# Motor_control_logic.net
KiCad netlist of a schematic drawn in Altium Designer
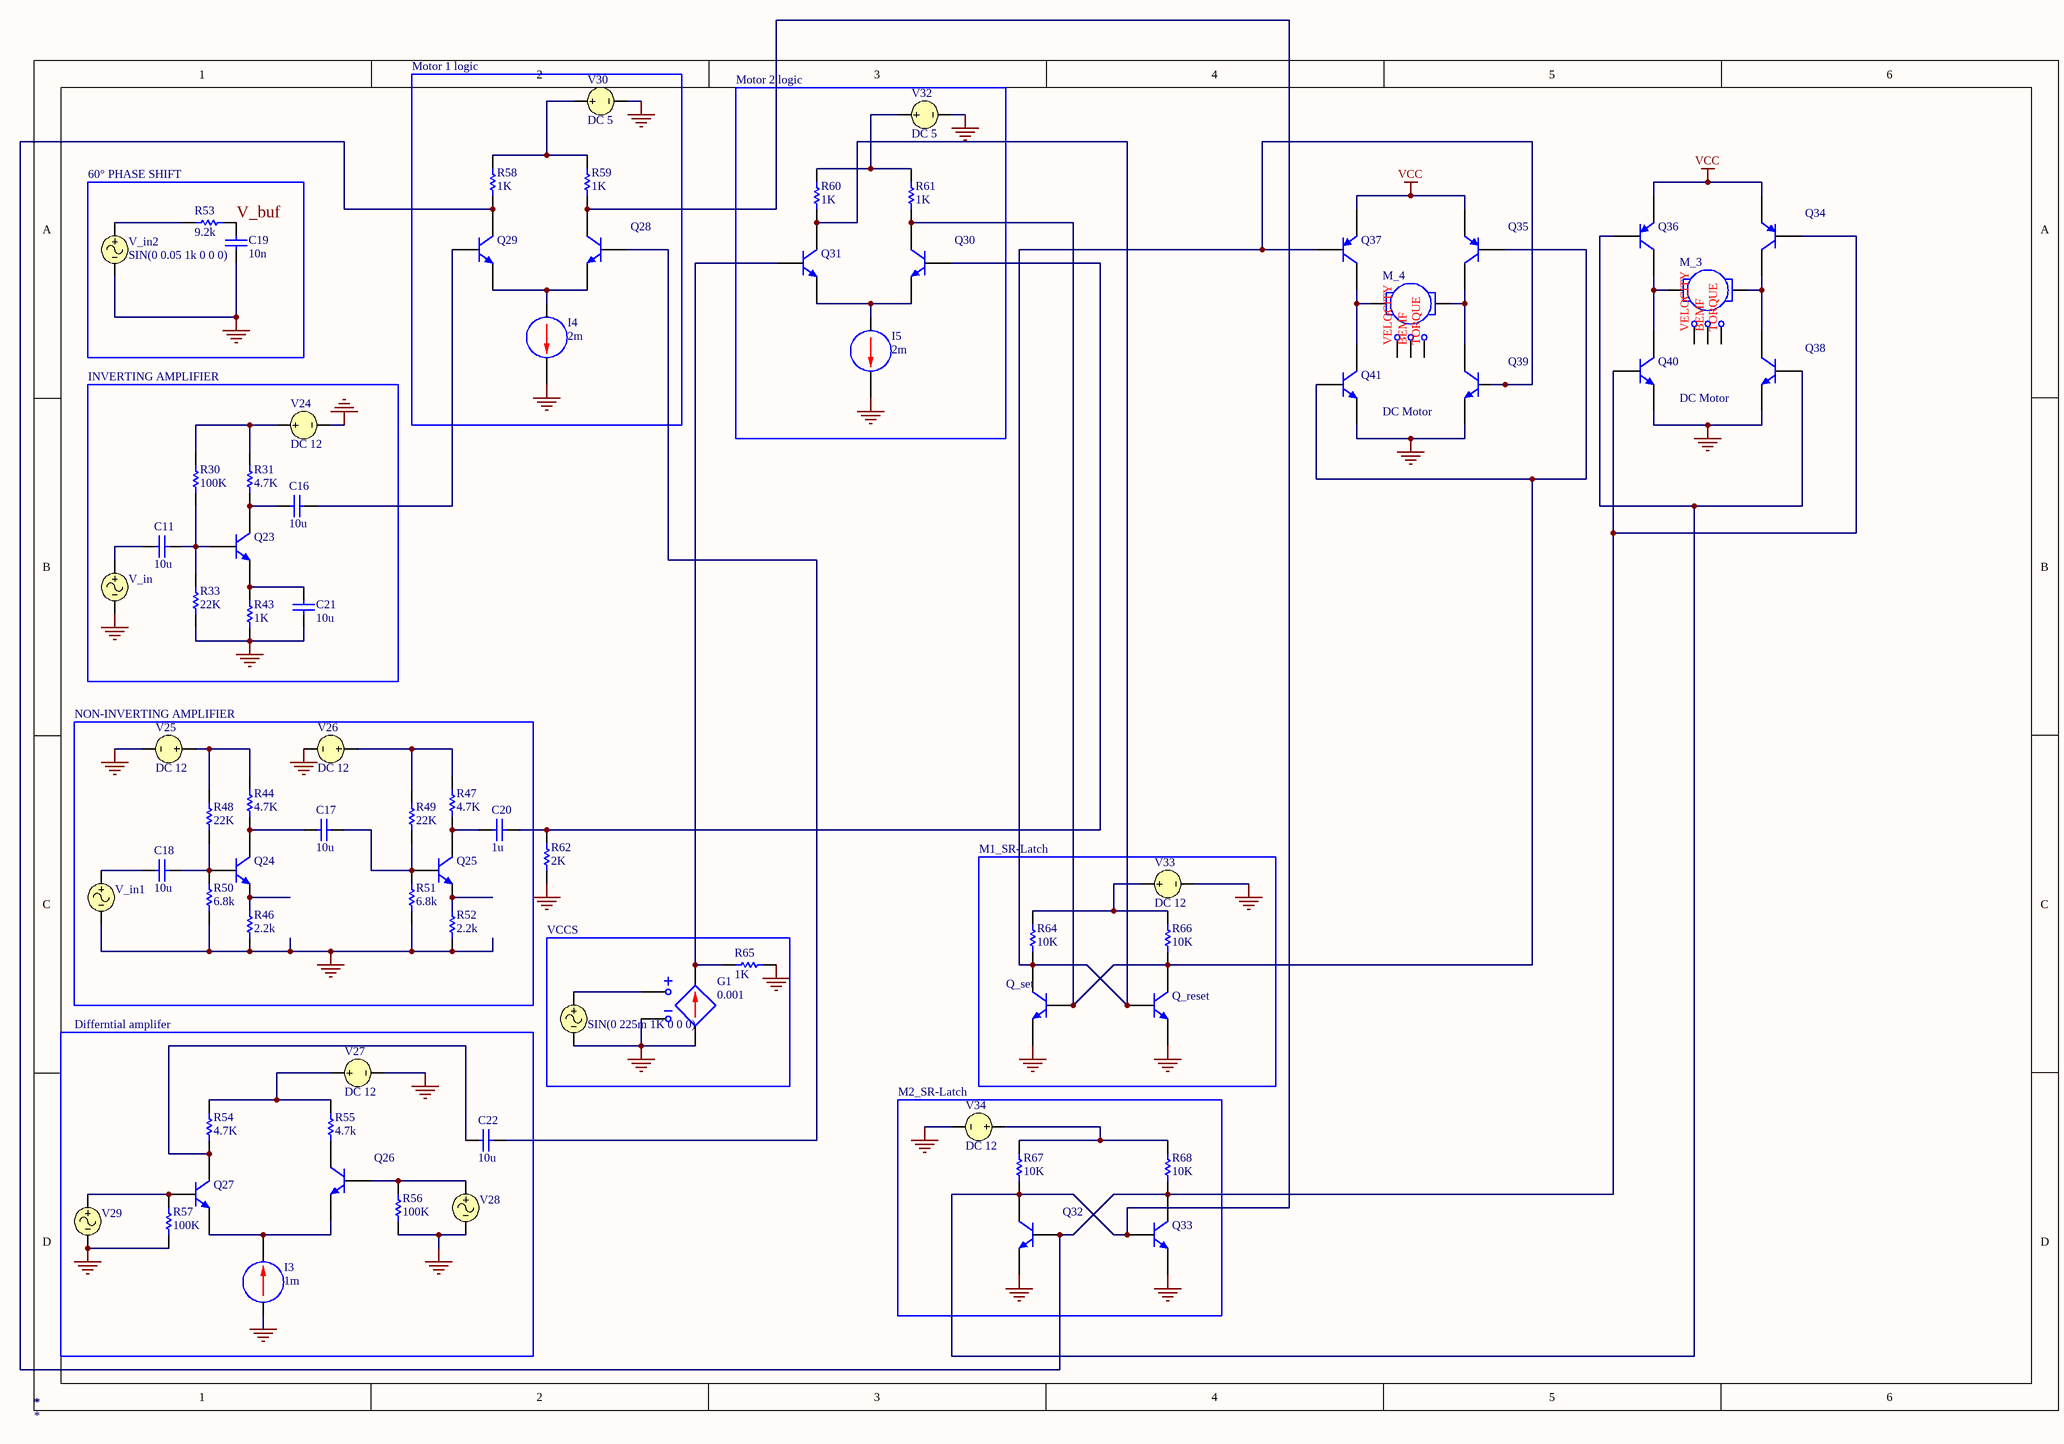
[diagram p0: Motor control logic.SchDoc]

(export (version "E")
  (design (tool "Eeschema 10.0.6"))
  (components
    (comp (ref "C11")
      (value "10u")
      (description "Capacitor")
      (libsource (lib "Simulation Generic Components") (part "Capacitor"))
    )
    (comp (ref "C16")
      (value "10u")
      (description "Capacitor")
      (libsource (lib "Simulation Generic Components") (part "Capacitor"))
    )
    (comp (ref "C17")
      (value "10u")
      (description "Capacitor")
      (libsource (lib "Simulation Generic Components") (part "Capacitor"))
    )
    (comp (ref "C18")
      (value "10u")
      (description "Capacitor")
      (libsource (lib "Simulation Generic Components") (part "Capacitor"))
    )
    (comp (ref "C19")
      (value "10n")
      (description "Capacitor")
      (libsource (lib "Simulation Generic Components") (part "Capacitor"))
    )
    (comp (ref "C20")
      (value "1u")
      (description "Capacitor")
      (libsource (lib "Simulation Generic Components") (part "Capacitor"))
    )
    (comp (ref "C21")
      (value "10u")
      (description "Capacitor")
      (libsource (lib "Simulation Generic Components") (part "Capacitor"))
    )
    (comp (ref "C22")
      (value "10u")
      (description "Capacitor")
      (libsource (lib "Simulation Generic Components") (part "Capacitor"))
    )
    (comp (ref "G1")
      (value "Voltage Controlled Current Source")
      (fields (field (name "GAIN") "0.001"))
      (libsource (lib "Simulation Generic Components") (part "VCCS"))
    )
    (comp (ref "I3")
      (value "DC Current Source")
      (fields (field (name "DC") "1m"))
      (libsource (lib "Simulation Generic Components") (part "DC Current Source"))
    )
    (comp (ref "I4")
      (value "DC Current Source")
      (fields (field (name "DC") "2m"))
      (libsource (lib "Simulation Generic Components") (part "DC Current Source"))
    )
    (comp (ref "I5")
      (value "DC Current Source")
      (fields (field (name "DC") "2m"))
      (libsource (lib "Simulation Generic Components") (part "DC Current Source"))
    )
    (comp (ref "M_3") (value "DC Motor") (libsource (lib "Simulation Generic Components") (part "DC Motor")))
    (comp (ref "M_4") (value "DC Motor") (libsource (lib "Simulation Generic Components") (part "DC Motor")))
    (comp (ref "Q23")
      (value "Bipolar NPN 3 Pins Transistor VBIC Model")
      (libsource (lib "Simulation Generic Components") (part "BJT NPN VBIC"))
    )
    (comp (ref "Q24")
      (value "Bipolar NPN 3 Pins Transistor Modified Version of the Gummel-Poon Model")
      (libsource (lib "Simulation Generic Components") (part "BJT NPN_MGP"))
    )
    (comp (ref "Q25")
      (value "Bipolar NPN 3 Pins Transistor Modified Version of the Gummel-Poon Model")
      (libsource (lib "Simulation Generic Components") (part "BJT NPN_MGP"))
    )
    (comp (ref "Q26")
      (value "Bipolar NPN 3 Pins Transistor VBIC Model")
      (libsource (lib "Simulation Generic Components") (part "BJT NPN VBIC"))
    )
    (comp (ref "Q27")
      (value "Bipolar NPN 3 Pins Transistor VBIC Model")
      (libsource (lib "Simulation Generic Components") (part "BJT NPN VBIC"))
    )
    (comp (ref "Q28")
      (value "Bipolar NPN 3 Pins Transistor Modified Version of the Gummel-Poon Model")
      (libsource (lib "Simulation Generic Components") (part "BJT NPN_MGP"))
    )
    (comp (ref "Q29")
      (value "Bipolar NPN 3 Pins Transistor Modified Version of the Gummel-Poon Model")
      (libsource (lib "Simulation Generic Components") (part "BJT NPN_MGP"))
    )
    (comp (ref "Q30")
      (value "Bipolar NPN 3 Pins Transistor Modified Version of the Gummel-Poon Model")
      (libsource (lib "Simulation Generic Components") (part "BJT NPN_MGP"))
    )
    (comp (ref "Q31")
      (value "Bipolar NPN 3 Pins Transistor Modified Version of the Gummel-Poon Model")
      (libsource (lib "Simulation Generic Components") (part "BJT NPN_MGP"))
    )
    (comp (ref "Q32")
      (value "Bipolar NPN 3 Pins Transistor VBIC Model")
      (libsource (lib "Simulation Generic Components") (part "BJT NPN VBIC"))
    )
    (comp (ref "Q33")
      (value "Bipolar NPN 3 Pins Transistor VBIC Model")
      (libsource (lib "Simulation Generic Components") (part "BJT NPN VBIC"))
    )
    (comp (ref "Q34")
      (value "Bipolar PNP 3 Pins Transistor Gummel-Poon Model")
      (libsource (lib "Simulation Generic Components") (part "BJT PNP GP"))
    )
    (comp (ref "Q35")
      (value "Bipolar PNP 3 Pins Transistor Gummel-Poon Model")
      (libsource (lib "Simulation Generic Components") (part "BJT PNP GP"))
    )
    (comp (ref "Q36")
      (value "Bipolar PNP 3 Pins Transistor Gummel-Poon Model")
      (libsource (lib "Simulation Generic Components") (part "BJT PNP GP"))
    )
    (comp (ref "Q37")
      (value "Bipolar PNP 3 Pins Transistor Gummel-Poon Model")
      (libsource (lib "Simulation Generic Components") (part "BJT PNP GP"))
    )
    (comp (ref "Q38")
      (value "Bipolar NPN 3 Pins Transistor VBIC Model")
      (libsource (lib "Simulation Generic Components") (part "BJT NPN VBIC"))
    )
    (comp (ref "Q39")
      (value "Bipolar NPN 3 Pins Transistor VBIC Model")
      (libsource (lib "Simulation Generic Components") (part "BJT NPN VBIC"))
    )
    (comp (ref "Q40")
      (value "Bipolar NPN 3 Pins Transistor VBIC Model")
      (libsource (lib "Simulation Generic Components") (part "BJT NPN VBIC"))
    )
    (comp (ref "Q41")
      (value "Bipolar NPN 3 Pins Transistor VBIC Model")
      (libsource (lib "Simulation Generic Components") (part "BJT NPN VBIC"))
    )
    (comp (ref "Q_reset")
      (value "Bipolar NPN 3 Pins Transistor VBIC Model")
      (libsource (lib "Simulation Generic Components") (part "BJT NPN VBIC"))
    )
    (comp (ref "Q_set")
      (value "Bipolar NPN 3 Pins Transistor VBIC Model")
      (libsource (lib "Simulation Generic Components") (part "BJT NPN VBIC"))
    )
    (comp (ref "R30")
      (value "100K")
      (description "Resistor")
      (libsource (lib "Simulation Generic Components") (part "Resistor"))
    )
    (comp (ref "R31")
      (value "4.7K")
      (description "Resistor")
      (libsource (lib "Simulation Generic Components") (part "Resistor"))
    )
    (comp (ref "R33")
      (value "22K")
      (description "Resistor")
      (libsource (lib "Simulation Generic Components") (part "Resistor"))
    )
    (comp (ref "R43")
      (value "1K")
      (description "Resistor")
      (libsource (lib "Simulation Generic Components") (part "Resistor"))
    )
    (comp (ref "R44")
      (value "4.7K")
      (description "Resistor")
      (libsource (lib "Simulation Generic Components") (part "Resistor"))
    )
    (comp (ref "R46")
      (value "2.2k")
      (description "Resistor")
      (libsource (lib "Simulation Generic Components") (part "Resistor"))
    )
    (comp (ref "R47")
      (value "4.7K")
      (description "Resistor")
      (libsource (lib "Simulation Generic Components") (part "Resistor"))
    )
    (comp (ref "R48")
      (value "22K")
      (description "Resistor")
      (libsource (lib "Simulation Generic Components") (part "Resistor"))
    )
    (comp (ref "R49")
      (value "22K")
      (description "Resistor")
      (libsource (lib "Simulation Generic Components") (part "Resistor"))
    )
    (comp (ref "R50")
      (value "6.8k")
      (description "Resistor")
      (libsource (lib "Simulation Generic Components") (part "Resistor"))
    )
    (comp (ref "R51")
      (value "6.8k")
      (description "Resistor")
      (libsource (lib "Simulation Generic Components") (part "Resistor"))
    )
    (comp (ref "R52")
      (value "2.2k")
      (description "Resistor")
      (libsource (lib "Simulation Generic Components") (part "Resistor"))
    )
    (comp (ref "R53")
      (value "9.2k")
      (description "Resistor")
      (libsource (lib "Simulation Generic Components") (part "Resistor"))
    )
    (comp (ref "R54")
      (value "4.7K")
      (description "Resistor")
      (libsource (lib "Simulation Generic Components") (part "Resistor"))
    )
    (comp (ref "R55")
      (value "4.7k")
      (description "Resistor")
      (libsource (lib "Simulation Generic Components") (part "Resistor"))
    )
    (comp (ref "R56")
      (value "100K")
      (description "Resistor")
      (libsource (lib "Simulation Generic Components") (part "Resistor"))
    )
    (comp (ref "R57")
      (value "100K")
      (description "Resistor")
      (libsource (lib "Simulation Generic Components") (part "Resistor"))
    )
    (comp (ref "R58")
      (value "1K")
      (description "Resistor")
      (libsource (lib "Simulation Generic Components") (part "Resistor"))
    )
    (comp (ref "R59")
      (value "1K")
      (description "Resistor")
      (libsource (lib "Simulation Generic Components") (part "Resistor"))
    )
    (comp (ref "R60")
      (value "1K")
      (description "Resistor")
      (libsource (lib "Simulation Generic Components") (part "Resistor"))
    )
    (comp (ref "R61")
      (value "1K")
      (description "Resistor")
      (libsource (lib "Simulation Generic Components") (part "Resistor"))
    )
    (comp (ref "R62")
      (value "2K")
      (description "Resistor")
      (libsource (lib "Simulation Generic Components") (part "Resistor"))
    )
    (comp (ref "R64")
      (value "10K")
      (description "Resistor")
      (libsource (lib "Simulation Generic Components") (part "Resistor"))
    )
    (comp (ref "R65")
      (value "1K")
      (description "Resistor")
      (libsource (lib "Simulation Generic Components") (part "Resistor"))
    )
    (comp (ref "R66")
      (value "10K")
      (description "Resistor")
      (libsource (lib "Simulation Generic Components") (part "Resistor"))
    )
    (comp (ref "R67")
      (value "10K")
      (description "Resistor")
      (libsource (lib "Simulation Generic Components") (part "Resistor"))
    )
    (comp (ref "R68")
      (value "10K")
      (description "Resistor")
      (libsource (lib "Simulation Generic Components") (part "Resistor"))
    )
    (comp (ref "V24")
      (value "DC 12")
      (description "Voltage Source")
      (fields (field (name "PUBLISHER") "Altium Limited"))
      (libsource (lib "Simulation Generic Components") (part "VSRC"))
    )
    (comp (ref "V25")
      (value "DC 12")
      (description "Voltage Source")
      (fields (field (name "PUBLISHER") "Altium Limited"))
      (libsource (lib "Simulation Generic Components") (part "VSRC"))
    )
    (comp (ref "V26")
      (value "DC 12")
      (description "Voltage Source")
      (fields (field (name "PUBLISHER") "Altium Limited"))
      (libsource (lib "Simulation Generic Components") (part "VSRC"))
    )
    (comp (ref "V27")
      (value "DC 12")
      (description "Voltage Source")
      (fields (field (name "PUBLISHER") "Altium Limited"))
      (libsource (lib "Simulation Generic Components") (part "VSRC"))
    )
    (comp (ref "V28")
      (value "SIN(0 50m 1K 0 0 60)")
      (description "Sinusoidal Voltage Source")
      (fields (field (name "PUBLISHER") "Altium Limited"))
      (libsource (lib "Simulation Generic Components") (part "VSIN"))
    )
    (comp (ref "V29")
      (value "SIN(0 50m 1K 0 0 0)")
      (description "Sinusoidal Voltage Source")
      (fields (field (name "PUBLISHER") "Altium Limited"))
      (libsource (lib "Simulation Generic Components") (part "VSIN"))
    )
    (comp (ref "V30")
      (value "DC 5")
      (description "Voltage Source")
      (fields (field (name "PUBLISHER") "Altium Limited"))
      (libsource (lib "Simulation Generic Components") (part "VSRC"))
    )
    (comp (ref "V31")
      (value "SIN(0 225m 1K 0 0 0)")
      (description "Sinusoidal Voltage Source")
      (fields (field (name "PUBLISHER") "Altium Limited"))
      (libsource (lib "Simulation Generic Components") (part "VSIN"))
    )
    (comp (ref "V32")
      (value "DC 5")
      (description "Voltage Source")
      (fields (field (name "PUBLISHER") "Altium Limited"))
      (libsource (lib "Simulation Generic Components") (part "VSRC"))
    )
    (comp (ref "V33")
      (value "DC 12")
      (description "Voltage Source")
      (fields (field (name "PUBLISHER") "Altium Limited"))
      (libsource (lib "Simulation Generic Components") (part "VSRC"))
    )
    (comp (ref "V34")
      (value "DC 12")
      (description "Voltage Source")
      (fields (field (name "PUBLISHER") "Altium Limited"))
      (libsource (lib "Simulation Generic Components") (part "VSRC"))
    )
    (comp (ref "V_in")
      (value "SIN(0 0.1 1K 0 0 0)")
      (description "Sinusoidal Voltage Source")
      (fields (field (name "PUBLISHER") "Altium Limited"))
      (libsource (lib "Simulation Generic Components") (part "VSIN"))
    )
    (comp (ref "V_in1")
      (value "SIN(0 0.1 1K 0 0 0)")
      (description "Sinusoidal Voltage Source")
      (fields (field (name "PUBLISHER") "Altium Limited"))
      (libsource (lib "Simulation Generic Components") (part "VSIN"))
    )
    (comp (ref "V_in2")
      (value "SIN(0 0.05 1k 0 0 0)")
      (description "Sinusoidal Voltage Source")
      (fields (field (name "PUBLISHER") "Altium Limited"))
      (libsource (lib "Simulation Generic Components") (part "VSIN"))
    )
  )
  (nets
    (net (code "1") (name "/V_buf") (class "Default")
      (node (ref "C19") (pin "2") (pinfunction "2_2") (pintype "passive"))
      (node (ref "R53") (pin "2") (pinfunction "2_2") (pintype "passive"))
    )
    (net (code "2") (name "GND") (class "Default")
      (node (ref "C19") (pin "1") (pinfunction "1_1") (pintype "passive"))
      (node (ref "C21") (pin "1") (pinfunction "1_1") (pintype "passive"))
      (node (ref "G1") (pin "2") (pinfunction "2_2") (pintype "passive"))
      (node (ref "G1") (pin "4") (pinfunction "4_4") (pintype "passive"))
      (node (ref "I3") (pin "2") (pinfunction "-_2") (pintype "passive"))
      (node (ref "I4") (pin "1") (pinfunction "+_1") (pintype "passive"))
      (node (ref "I5") (pin "1") (pinfunction "+_1") (pintype "passive"))
      (node (ref "Q32") (pin "3") (pinfunction "E_3") (pintype "passive"))
      (node (ref "Q33") (pin "3") (pinfunction "E_3") (pintype "passive"))
      (node (ref "Q38") (pin "3") (pinfunction "E_3") (pintype "passive"))
      (node (ref "Q39") (pin "3") (pinfunction "E_3") (pintype "passive"))
      (node (ref "Q40") (pin "3") (pinfunction "E_3") (pintype "passive"))
      (node (ref "Q41") (pin "3") (pinfunction "E_3") (pintype "passive"))
      (node (ref "Q_reset") (pin "3") (pinfunction "E_3") (pintype "passive"))
      (node (ref "Q_set") (pin "3") (pinfunction "E_3") (pintype "passive"))
      (node (ref "R33") (pin "1") (pinfunction "1_1") (pintype "passive"))
      (node (ref "R43") (pin "1") (pinfunction "1_1") (pintype "passive"))
      (node (ref "R46") (pin "1") (pinfunction "1_1") (pintype "passive"))
      (node (ref "R50") (pin "1") (pinfunction "1_1") (pintype "passive"))
      (node (ref "R51") (pin "1") (pinfunction "1_1") (pintype "passive"))
      (node (ref "R52") (pin "1") (pinfunction "1_1") (pintype "passive"))
      (node (ref "R56") (pin "1") (pinfunction "1_1") (pintype "passive"))
      (node (ref "R57") (pin "1") (pinfunction "1_1") (pintype "passive"))
      (node (ref "R62") (pin "1") (pinfunction "1_1") (pintype "passive"))
      (node (ref "R65") (pin "2") (pinfunction "2_2") (pintype "passive"))
      (node (ref "V24") (pin "2") (pinfunction "2_2") (pintype "passive"))
      (node (ref "V25") (pin "2") (pinfunction "2_2") (pintype "passive"))
      (node (ref "V26") (pin "2") (pinfunction "2_2") (pintype "passive"))
      (node (ref "V27") (pin "2") (pinfunction "2_2") (pintype "passive"))
      (node (ref "V28") (pin "2") (pinfunction "2_2") (pintype "passive"))
      (node (ref "V29") (pin "2") (pinfunction "2_2") (pintype "passive"))
      (node (ref "V30") (pin "2") (pinfunction "2_2") (pintype "passive"))
      (node (ref "V31") (pin "2") (pinfunction "2_2") (pintype "passive"))
      (node (ref "V32") (pin "2") (pinfunction "2_2") (pintype "passive"))
      (node (ref "V33") (pin "2") (pinfunction "2_2") (pintype "passive"))
      (node (ref "V34") (pin "2") (pinfunction "2_2") (pintype "passive"))
      (node (ref "V_in") (pin "2") (pinfunction "2_2") (pintype "passive"))
      (node (ref "V_in1") (pin "2") (pinfunction "2_2") (pintype "passive"))
      (node (ref "V_in2") (pin "2") (pinfunction "2_2") (pintype "passive"))
    )
    (net (code "3") (name "Net-(C11-Pad1)") (class "Default")
      (node (ref "C11") (pin "1") (pinfunction "1_1") (pintype "passive"))
      (node (ref "V_in") (pin "1") (pinfunction "1_1") (pintype "passive"))
    )
    (net (code "4") (name "Net-(C18-Pad1)") (class "Default")
      (node (ref "C18") (pin "1") (pinfunction "1_1") (pintype "passive"))
      (node (ref "V_in1") (pin "1") (pinfunction "1_1") (pintype "passive"))
    )
    (net (code "5") (name "Net-(G1-Pad3)") (class "Default")
      (node (ref "G1") (pin "3") (pinfunction "3_3") (pintype "passive"))
      (node (ref "V31") (pin "1") (pinfunction "1_1") (pintype "passive"))
    )
    (net (code "6") (name "Net-(I3-+)") (class "Default")
      (node (ref "I3") (pin "1") (pinfunction "+_1") (pintype "passive"))
      (node (ref "Q26") (pin "3") (pinfunction "E_3") (pintype "passive"))
      (node (ref "Q27") (pin "3") (pinfunction "E_3") (pintype "passive"))
    )
    (net (code "7") (name "Net-(I4--)") (class "Default")
      (node (ref "I4") (pin "2") (pinfunction "-_2") (pintype "passive"))
      (node (ref "Q28") (pin "3") (pinfunction "E_3") (pintype "passive"))
      (node (ref "Q29") (pin "3") (pinfunction "E_3") (pintype "passive"))
    )
    (net (code "8") (name "Net-(I5--)") (class "Default")
      (node (ref "I5") (pin "2") (pinfunction "-_2") (pintype "passive"))
      (node (ref "Q30") (pin "3") (pinfunction "E_3") (pintype "passive"))
      (node (ref "Q31") (pin "3") (pinfunction "E_3") (pintype "passive"))
    )
    (net (code "9") (name "Net-(Q23-B)") (class "Default")
      (node (ref "C11") (pin "2") (pinfunction "2_2") (pintype "passive"))
      (node (ref "Q23") (pin "2") (pinfunction "B_2") (pintype "passive"))
      (node (ref "R30") (pin "1") (pinfunction "1_1") (pintype "passive"))
      (node (ref "R33") (pin "2") (pinfunction "2_2") (pintype "passive"))
    )
    (net (code "10") (name "Net-(Q23-C)") (class "Default")
      (node (ref "C16") (pin "1") (pinfunction "1_1") (pintype "passive"))
      (node (ref "Q23") (pin "1") (pinfunction "C_1") (pintype "passive"))
      (node (ref "R31") (pin "1") (pinfunction "1_1") (pintype "passive"))
    )
    (net (code "11") (name "Net-(Q23-E)") (class "Default")
      (node (ref "C21") (pin "2") (pinfunction "2_2") (pintype "passive"))
      (node (ref "Q23") (pin "3") (pinfunction "E_3") (pintype "passive"))
      (node (ref "R43") (pin "2") (pinfunction "2_2") (pintype "passive"))
    )
    (net (code "12") (name "Net-(Q24-B)") (class "Default")
      (node (ref "C18") (pin "2") (pinfunction "2_2") (pintype "passive"))
      (node (ref "Q24") (pin "2") (pinfunction "B_2") (pintype "passive"))
      (node (ref "R48") (pin "1") (pinfunction "1_1") (pintype "passive"))
      (node (ref "R50") (pin "2") (pinfunction "2_2") (pintype "passive"))
    )
    (net (code "13") (name "Net-(Q24-C)") (class "Default")
      (node (ref "C17") (pin "1") (pinfunction "1_1") (pintype "passive"))
      (node (ref "Q24") (pin "1") (pinfunction "C_1") (pintype "passive"))
      (node (ref "R44") (pin "1") (pinfunction "1_1") (pintype "passive"))
    )
    (net (code "14") (name "Net-(Q24-E)") (class "Default")
      (node (ref "Q24") (pin "3") (pinfunction "E_3") (pintype "passive"))
      (node (ref "R46") (pin "2") (pinfunction "2_2") (pintype "passive"))
    )
    (net (code "15") (name "Net-(Q25-B)") (class "Default")
      (node (ref "C17") (pin "2") (pinfunction "2_2") (pintype "passive"))
      (node (ref "Q25") (pin "2") (pinfunction "B_2") (pintype "passive"))
      (node (ref "R49") (pin "1") (pinfunction "1_1") (pintype "passive"))
      (node (ref "R51") (pin "2") (pinfunction "2_2") (pintype "passive"))
    )
    (net (code "16") (name "Net-(Q25-C)") (class "Default")
      (node (ref "C20") (pin "1") (pinfunction "1_1") (pintype "passive"))
      (node (ref "Q25") (pin "1") (pinfunction "C_1") (pintype "passive"))
      (node (ref "R47") (pin "1") (pinfunction "1_1") (pintype "passive"))
    )
    (net (code "17") (name "Net-(Q25-E)") (class "Default")
      (node (ref "Q25") (pin "3") (pinfunction "E_3") (pintype "passive"))
      (node (ref "R52") (pin "2") (pinfunction "2_2") (pintype "passive"))
    )
    (net (code "18") (name "Net-(Q26-B)") (class "Default")
      (node (ref "Q26") (pin "2") (pinfunction "B_2") (pintype "passive"))
      (node (ref "R56") (pin "2") (pinfunction "2_2") (pintype "passive"))
      (node (ref "V28") (pin "1") (pinfunction "1_1") (pintype "passive"))
    )
    (net (code "19") (name "Net-(Q27-B)") (class "Default")
      (node (ref "Q27") (pin "2") (pinfunction "B_2") (pintype "passive"))
      (node (ref "R57") (pin "2") (pinfunction "2_2") (pintype "passive"))
      (node (ref "V29") (pin "1") (pinfunction "1_1") (pintype "passive"))
    )
    (net (code "20") (name "Net-(Q27-C)") (class "Default")
      (node (ref "C22") (pin "1") (pinfunction "1_1") (pintype "passive"))
      (node (ref "Q27") (pin "1") (pinfunction "C_1") (pintype "passive"))
      (node (ref "R54") (pin "1") (pinfunction "1_1") (pintype "passive"))
    )
    (net (code "21") (name "Net-(Q28-B)") (class "Default")
      (node (ref "C22") (pin "2") (pinfunction "2_2") (pintype "passive"))
      (node (ref "Q28") (pin "2") (pinfunction "B_2") (pintype "passive"))
    )
    (net (code "22") (name "Net-(Q28-C)") (class "Default")
      (node (ref "Q28") (pin "1") (pinfunction "C_1") (pintype "passive"))
      (node (ref "Q32") (pin "1") (pinfunction "C_1") (pintype "passive"))
      (node (ref "Q33") (pin "2") (pinfunction "B_2") (pintype "passive"))
      (node (ref "Q36") (pin "2") (pinfunction "B_2") (pintype "passive"))
      (node (ref "Q38") (pin "2") (pinfunction "B_2") (pintype "passive"))
      (node (ref "R59") (pin "1") (pinfunction "1_1") (pintype "passive"))
      (node (ref "R67") (pin "1") (pinfunction "1_1") (pintype "passive"))
    )
    (net (code "23") (name "Net-(Q29-B)") (class "Default")
      (node (ref "C16") (pin "2") (pinfunction "2_2") (pintype "passive"))
      (node (ref "Q29") (pin "2") (pinfunction "B_2") (pintype "passive"))
    )
    (net (code "24") (name "Net-(Q29-C)") (class "Default")
      (node (ref "Q29") (pin "1") (pinfunction "C_1") (pintype "passive"))
      (node (ref "Q32") (pin "2") (pinfunction "B_2") (pintype "passive"))
      (node (ref "Q33") (pin "1") (pinfunction "C_1") (pintype "passive"))
      (node (ref "Q34") (pin "2") (pinfunction "B_2") (pintype "passive"))
      (node (ref "Q40") (pin "2") (pinfunction "B_2") (pintype "passive"))
      (node (ref "R58") (pin "1") (pinfunction "1_1") (pintype "passive"))
      (node (ref "R68") (pin "1") (pinfunction "1_1") (pintype "passive"))
    )
    (net (code "25") (name "Net-(Q30-B)") (class "Default")
      (node (ref "C20") (pin "2") (pinfunction "2_2") (pintype "passive"))
      (node (ref "Q30") (pin "2") (pinfunction "B_2") (pintype "passive"))
      (node (ref "R62") (pin "2") (pinfunction "2_2") (pintype "passive"))
    )
    (net (code "26") (name "Net-(Q30-C)") (class "Default")
      (node (ref "Q30") (pin "1") (pinfunction "C_1") (pintype "passive"))
      (node (ref "Q35") (pin "2") (pinfunction "B_2") (pintype "passive"))
      (node (ref "Q41") (pin "2") (pinfunction "B_2") (pintype "passive"))
      (node (ref "Q_reset") (pin "1") (pinfunction "C_1") (pintype "passive"))
      (node (ref "Q_set") (pin "2") (pinfunction "B_2") (pintype "passive"))
      (node (ref "R61") (pin "1") (pinfunction "1_1") (pintype "passive"))
      (node (ref "R66") (pin "1") (pinfunction "1_1") (pintype "passive"))
    )
    (net (code "27") (name "Net-(Q31-B)") (class "Default")
      (node (ref "G1") (pin "1") (pinfunction "1_1") (pintype "passive"))
      (node (ref "Q31") (pin "2") (pinfunction "B_2") (pintype "passive"))
      (node (ref "R65") (pin "1") (pinfunction "1_1") (pintype "passive"))
    )
    (net (code "28") (name "Net-(Q31-C)") (class "Default")
      (node (ref "Q31") (pin "1") (pinfunction "C_1") (pintype "passive"))
      (node (ref "Q37") (pin "2") (pinfunction "B_2") (pintype "passive"))
      (node (ref "Q39") (pin "2") (pinfunction "B_2") (pintype "passive"))
      (node (ref "Q_reset") (pin "2") (pinfunction "B_2") (pintype "passive"))
      (node (ref "Q_set") (pin "1") (pinfunction "C_1") (pintype "passive"))
      (node (ref "R60") (pin "1") (pinfunction "1_1") (pintype "passive"))
      (node (ref "R64") (pin "1") (pinfunction "1_1") (pintype "passive"))
    )
    (net (code "29") (name "Net-(Q34-C)") (class "Default")
      (node (ref "M_3") (pin "2") (pinfunction "2_2") (pintype "passive"))
      (node (ref "Q34") (pin "1") (pinfunction "C_1") (pintype "passive"))
      (node (ref "Q38") (pin "1") (pinfunction "C_1") (pintype "passive"))
    )
    (net (code "30") (name "Net-(Q35-C)") (class "Default")
      (node (ref "M_4") (pin "2") (pinfunction "2_2") (pintype "passive"))
      (node (ref "Q35") (pin "1") (pinfunction "C_1") (pintype "passive"))
      (node (ref "Q39") (pin "1") (pinfunction "C_1") (pintype "passive"))
    )
    (net (code "31") (name "Net-(Q36-C)") (class "Default")
      (node (ref "M_3") (pin "1") (pinfunction "1_1") (pintype "passive"))
      (node (ref "Q36") (pin "1") (pinfunction "C_1") (pintype "passive"))
      (node (ref "Q40") (pin "1") (pinfunction "C_1") (pintype "passive"))
    )
    (net (code "32") (name "Net-(Q37-C)") (class "Default")
      (node (ref "M_4") (pin "1") (pinfunction "1_1") (pintype "passive"))
      (node (ref "Q37") (pin "1") (pinfunction "C_1") (pintype "passive"))
      (node (ref "Q41") (pin "1") (pinfunction "C_1") (pintype "passive"))
    )
    (net (code "33") (name "Net-(R30-Pad2)") (class "Default")
      (node (ref "R30") (pin "2") (pinfunction "2_2") (pintype "passive"))
      (node (ref "R31") (pin "2") (pinfunction "2_2") (pintype "passive"))
      (node (ref "V24") (pin "1") (pinfunction "1_1") (pintype "passive"))
    )
    (net (code "34") (name "Net-(R44-Pad2)") (class "Default")
      (node (ref "R44") (pin "2") (pinfunction "2_2") (pintype "passive"))
      (node (ref "R48") (pin "2") (pinfunction "2_2") (pintype "passive"))
      (node (ref "V25") (pin "1") (pinfunction "1_1") (pintype "passive"))
    )
    (net (code "35") (name "Net-(R47-Pad2)") (class "Default")
      (node (ref "R47") (pin "2") (pinfunction "2_2") (pintype "passive"))
      (node (ref "R49") (pin "2") (pinfunction "2_2") (pintype "passive"))
      (node (ref "V26") (pin "1") (pinfunction "1_1") (pintype "passive"))
    )
    (net (code "36") (name "Net-(R53-Pad1)") (class "Default")
      (node (ref "R53") (pin "1") (pinfunction "1_1") (pintype "passive"))
      (node (ref "V_in2") (pin "1") (pinfunction "1_1") (pintype "passive"))
    )
    (net (code "37") (name "Net-(R54-Pad2)") (class "Default")
      (node (ref "R54") (pin "2") (pinfunction "2_2") (pintype "passive"))
      (node (ref "R55") (pin "2") (pinfunction "2_2") (pintype "passive"))
      (node (ref "V27") (pin "1") (pinfunction "1_1") (pintype "passive"))
    )
    (net (code "38") (name "Net-(R58-Pad2)") (class "Default")
      (node (ref "R58") (pin "2") (pinfunction "2_2") (pintype "passive"))
      (node (ref "R59") (pin "2") (pinfunction "2_2") (pintype "passive"))
      (node (ref "V30") (pin "1") (pinfunction "1_1") (pintype "passive"))
    )
    (net (code "39") (name "Net-(R60-Pad2)") (class "Default")
      (node (ref "R60") (pin "2") (pinfunction "2_2") (pintype "passive"))
      (node (ref "R61") (pin "2") (pinfunction "2_2") (pintype "passive"))
      (node (ref "V32") (pin "1") (pinfunction "1_1") (pintype "passive"))
    )
    (net (code "40") (name "Net-(R64-Pad2)") (class "Default")
      (node (ref "R64") (pin "2") (pinfunction "2_2") (pintype "passive"))
      (node (ref "R66") (pin "2") (pinfunction "2_2") (pintype "passive"))
      (node (ref "V33") (pin "1") (pinfunction "1_1") (pintype "passive"))
    )
    (net (code "41") (name "Net-(R67-Pad2)") (class "Default")
      (node (ref "R67") (pin "2") (pinfunction "2_2") (pintype "passive"))
      (node (ref "R68") (pin "2") (pinfunction "2_2") (pintype "passive"))
      (node (ref "V34") (pin "1") (pinfunction "1_1") (pintype "passive"))
    )
    (net (code "42") (name "VCC") (class "Default")
      (node (ref "Q34") (pin "3") (pinfunction "E_3") (pintype "passive"))
      (node (ref "Q35") (pin "3") (pinfunction "E_3") (pintype "passive"))
      (node (ref "Q36") (pin "3") (pinfunction "E_3") (pintype "passive"))
      (node (ref "Q37") (pin "3") (pinfunction "E_3") (pintype "passive"))
    )
    (net (code "43") (name "unconnected-(M_3-Pad3)") (class "Default")
      (node (ref "M_3") (pin "3") (pinfunction "3_3") (pintype "passive"))
    )
    (net (code "44") (name "unconnected-(M_3-Pad4)") (class "Default")
      (node (ref "M_3") (pin "4") (pinfunction "4_4") (pintype "passive"))
    )
    (net (code "45") (name "unconnected-(M_3-Pad5)") (class "Default")
      (node (ref "M_3") (pin "5") (pinfunction "5_5") (pintype "passive"))
    )
    (net (code "46") (name "unconnected-(M_4-Pad3)") (class "Default")
      (node (ref "M_4") (pin "3") (pinfunction "3_3") (pintype "passive"))
    )
    (net (code "47") (name "unconnected-(M_4-Pad4)") (class "Default")
      (node (ref "M_4") (pin "4") (pinfunction "4_4") (pintype "passive"))
    )
    (net (code "48") (name "unconnected-(M_4-Pad5)") (class "Default")
      (node (ref "M_4") (pin "5") (pinfunction "5_5") (pintype "passive"))
    )
    (net (code "49") (name "unconnected-(Q26-C-Pad1)") (class "Default")
      (node (ref "Q26") (pin "1") (pinfunction "C_1") (pintype "passive"))
    )
    (net (code "50") (name "unconnected-(R55-Pad1)") (class "Default")
      (node (ref "R55") (pin "1") (pinfunction "1_1") (pintype "passive"))
    )
  )
)
